# Schematics.net
KiCad netlist of a schematic drawn in Altium Designer
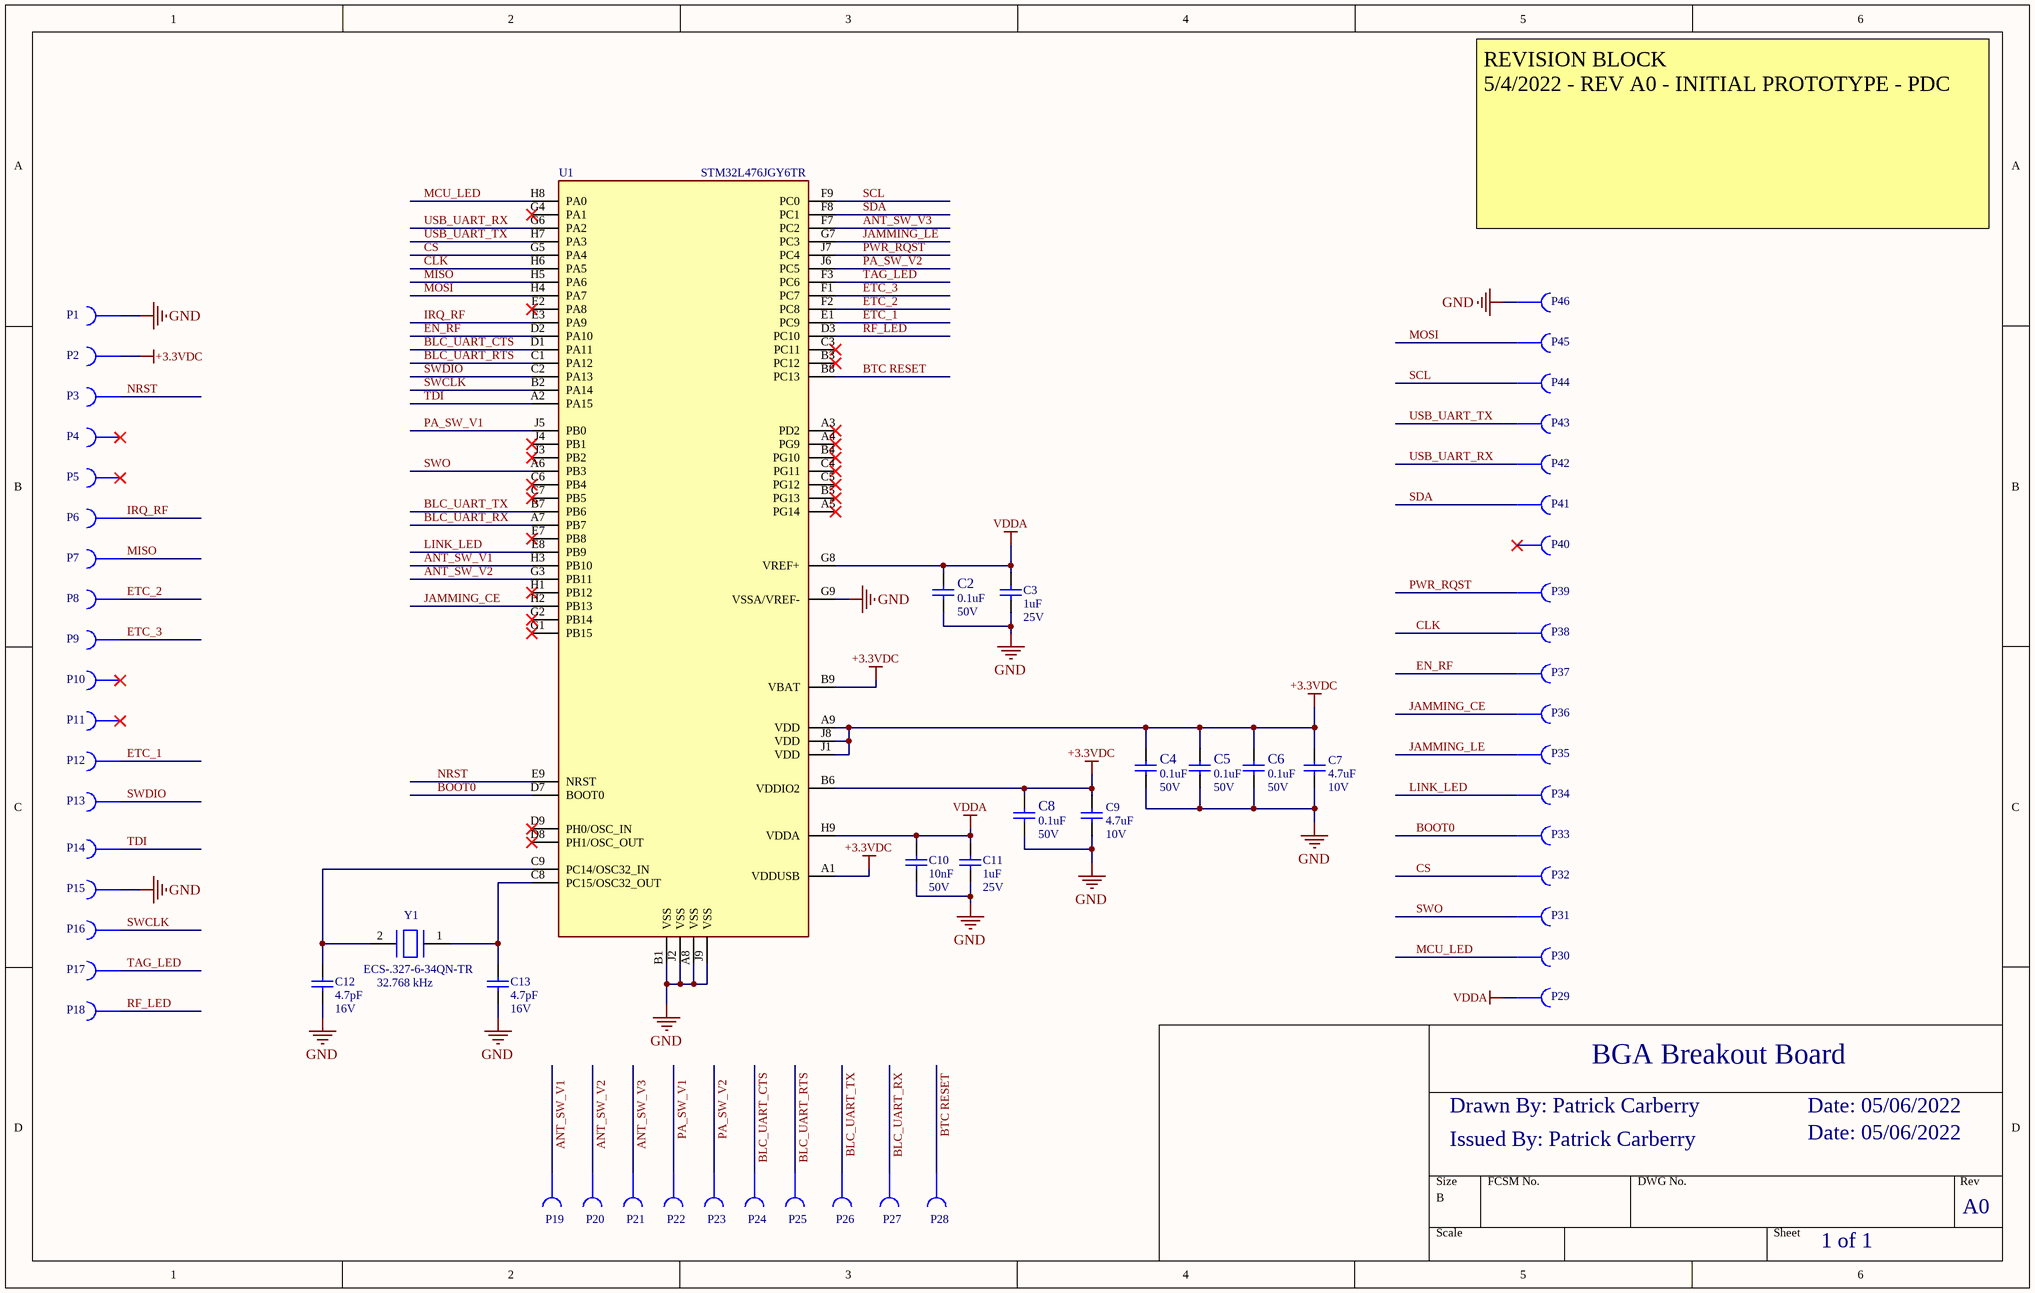
[diagram p0: Schematics.SchDoc]

(export (version "E")
  (design (tool "Eeschema 10.0.6"))
  (components
    (comp (ref "C2")
      (value "0.1uF")
      (footprint "CAP_0402_0.55MM")
      (description "CAP_0.1UF_50V_20%_0402")
      (fields
        (field (name "VOLTAGE RATING") "50V")
        (field (name "MANUFACTURER PART NUMBER") "GRM155R71H104KE14J")
        (field (name "MANUFACTURER") "Murata")
      )
      (libsource (lib "Schlib1") (part "CAP_0.1UF_50V_20%_0402"))
    )
    (comp (ref "C3")
      (value "1uF")
      (footprint "CAP_0402_0.55MM")
      (description "CAP_1UF_25V_20%_0402")
      (fields
        (field (name "MANUFACTURER") "Murata")
        (field (name "MANUFACTURER PART NUMBER") "GRM155R61E105MA12D")
        (field (name "VOLTAGE RATING") "25V")
      )
      (libsource (lib "Schlib1") (part "CAP_1UF_25V_20%_0402"))
    )
    (comp (ref "C4")
      (value "0.1uF")
      (footprint "CAP_0402_0.55MM")
      (description "CAP_0.1UF_50V_20%_0402")
      (fields
        (field (name "VOLTAGE RATING") "50V")
        (field (name "MANUFACTURER PART NUMBER") "GRM155R71H104KE14J")
        (field (name "MANUFACTURER") "Murata")
      )
      (libsource (lib "Schlib1") (part "CAP_0.1UF_50V_20%_0402"))
    )
    (comp (ref "C5")
      (value "0.1uF")
      (footprint "CAP_0402_0.55MM")
      (description "CAP_0.1UF_50V_20%_0402")
      (fields
        (field (name "VOLTAGE RATING") "50V")
        (field (name "MANUFACTURER PART NUMBER") "GRM155R71H104KE14J")
        (field (name "MANUFACTURER") "Murata")
      )
      (libsource (lib "Schlib1") (part "CAP_0.1UF_50V_20%_0402"))
    )
    (comp (ref "C6")
      (value "0.1uF")
      (footprint "CAP_0402_0.55MM")
      (description "CAP_0.1UF_50V_20%_0402")
      (fields
        (field (name "VOLTAGE RATING") "50V")
        (field (name "MANUFACTURER PART NUMBER") "GRM155R71H104KE14J")
        (field (name "MANUFACTURER") "Murata")
      )
      (libsource (lib "Schlib1") (part "CAP_0.1UF_50V_20%_0402"))
    )
    (comp (ref "C7")
      (value "4.7uF")
      (footprint "CAP_0402_0.55MM")
      (description "CAP CER 4.7UF 10V X5R 0402")
      (fields
        (field (name "MANUFACTURER") "Samsung Electro-Mechanics")
        (field (name "MANUFACTURER PART NUMBER") "CL05A475KP5NRNC")
        (field (name "VOLTAGE RATING") "10V")
      )
      (libsource (lib "Schlib1") (part "CAP_4.7UF_10V_X5R_0402"))
    )
    (comp (ref "C8")
      (value "0.1uF")
      (footprint "CAP_0402_0.55MM")
      (description "CAP_0.1UF_50V_20%_0402")
      (fields
        (field (name "VOLTAGE RATING") "50V")
        (field (name "MANUFACTURER PART NUMBER") "GRM155R71H104KE14J")
        (field (name "MANUFACTURER") "Murata")
      )
      (libsource (lib "Schlib1") (part "CAP_0.1UF_50V_20%_0402"))
    )
    (comp (ref "C9")
      (value "4.7uF")
      (footprint "CAP_0402_0.55MM")
      (description "CAP CER 4.7UF 10V X5R 0402")
      (fields
        (field (name "MANUFACTURER") "Samsung Electro-Mechanics")
        (field (name "MANUFACTURER PART NUMBER") "CL05A475KP5NRNC")
        (field (name "VOLTAGE RATING") "10V")
      )
      (libsource (lib "Schlib1") (part "CAP_4.7UF_10V_X5R_0402"))
    )
    (comp (ref "C10")
      (value "10nF")
      (footprint "CAP_0402_0.55MM")
      (description "CAP_10NF_50V_10%_0402")
      (fields
        (field (name "MANUFACTURER") "Murata")
        (field (name "MANUFACTURER PART NUMBER") "GCM155R71H103KA55J")
        (field (name "VOLTAGE RATING") "50V")
      )
      (libsource (lib "Schlib1") (part "CAP_10NF_50V_10%_0402"))
    )
    (comp (ref "C11")
      (value "1uF")
      (footprint "CAP_0402_0.55MM")
      (description "CAP_1UF_25V_20%_0402")
      (fields
        (field (name "MANUFACTURER") "Murata")
        (field (name "MANUFACTURER PART NUMBER") "GRM155R61E105MA12D")
        (field (name "VOLTAGE RATING") "25V")
      )
      (libsource (lib "Schlib1") (part "CAP_1UF_25V_20%_0402"))
    )
    (comp (ref "C12")
      (value "4.7pF")
      (footprint "CAP_0402_0.55MM")
      (description "CAP_4.7PF_16V_C0G_0402")
      (fields
        (field (name "MANUFACTURER") "Würth Elektronik")
        (field (name "MANUFACTURER PART NUMBER") "885012005023")
        (field (name "VOLTAGE RATING") "16V")
      )
      (libsource (lib "Schlib1") (part "CAP_4.7PF_16V_C0G_0402"))
    )
    (comp (ref "C13")
      (value "4.7pF")
      (footprint "CAP_0402_0.55MM")
      (description "CAP_4.7PF_16V_C0G_0402")
      (fields
        (field (name "MANUFACTURER") "Würth Elektronik")
        (field (name "MANUFACTURER PART NUMBER") "885012005023")
        (field (name "VOLTAGE RATING") "16V")
      )
      (libsource (lib "Schlib1") (part "CAP_4.7PF_16V_C0G_0402"))
    )
    (comp (ref "P1")
      (value "1-PIN-HDR-GEN")
      (footprint "1X01-PIN")
      (description "Generic through hole")
      (fields (field (name "MANUFACTURER PART NUMBER") "DNP"))
      (libsource (lib "Schlib1") (part "1-PIN-HDR-GEN"))
    )
    (comp (ref "P2")
      (value "1-PIN-HDR-GEN")
      (footprint "1X01-PIN")
      (description "Generic through hole")
      (fields (field (name "MANUFACTURER PART NUMBER") "DNP"))
      (libsource (lib "Schlib1") (part "1-PIN-HDR-GEN"))
    )
    (comp (ref "P3")
      (value "1-PIN-HDR-GEN")
      (footprint "1X01-PIN")
      (description "Generic through hole")
      (fields (field (name "MANUFACTURER PART NUMBER") "DNP"))
      (libsource (lib "Schlib1") (part "1-PIN-HDR-GEN"))
    )
    (comp (ref "P4")
      (value "1-PIN-HDR-GEN")
      (footprint "1X01-PIN")
      (description "Generic through hole")
      (fields (field (name "MANUFACTURER PART NUMBER") "DNP"))
      (libsource (lib "Schlib1") (part "1-PIN-HDR-GEN"))
    )
    (comp (ref "P5")
      (value "1-PIN-HDR-GEN")
      (footprint "1X01-PIN")
      (description "Generic through hole")
      (fields (field (name "MANUFACTURER PART NUMBER") "DNP"))
      (libsource (lib "Schlib1") (part "1-PIN-HDR-GEN"))
    )
    (comp (ref "P6")
      (value "1-PIN-HDR-GEN")
      (footprint "1X01-PIN")
      (description "Generic through hole")
      (fields (field (name "MANUFACTURER PART NUMBER") "DNP"))
      (libsource (lib "Schlib1") (part "1-PIN-HDR-GEN"))
    )
    (comp (ref "P7")
      (value "1-PIN-HDR-GEN")
      (footprint "1X01-PIN")
      (description "Generic through hole")
      (fields (field (name "MANUFACTURER PART NUMBER") "DNP"))
      (libsource (lib "Schlib1") (part "1-PIN-HDR-GEN"))
    )
    (comp (ref "P8")
      (value "1-PIN-HDR-GEN")
      (footprint "1X01-PIN")
      (description "Generic through hole")
      (fields (field (name "MANUFACTURER PART NUMBER") "DNP"))
      (libsource (lib "Schlib1") (part "1-PIN-HDR-GEN"))
    )
    (comp (ref "P9")
      (value "1-PIN-HDR-GEN")
      (footprint "1X01-PIN")
      (description "Generic through hole")
      (fields (field (name "MANUFACTURER PART NUMBER") "DNP"))
      (libsource (lib "Schlib1") (part "1-PIN-HDR-GEN"))
    )
    (comp (ref "P10")
      (value "1-PIN-HDR-GEN")
      (footprint "1X01-PIN")
      (description "Generic through hole")
      (fields (field (name "MANUFACTURER PART NUMBER") "DNP"))
      (libsource (lib "Schlib1") (part "1-PIN-HDR-GEN"))
    )
    (comp (ref "P11")
      (value "1-PIN-HDR-GEN")
      (footprint "1X01-PIN")
      (description "Generic through hole")
      (fields (field (name "MANUFACTURER PART NUMBER") "DNP"))
      (libsource (lib "Schlib1") (part "1-PIN-HDR-GEN"))
    )
    (comp (ref "P12")
      (value "1-PIN-HDR-GEN")
      (footprint "1X01-PIN")
      (description "Generic through hole")
      (fields (field (name "MANUFACTURER PART NUMBER") "DNP"))
      (libsource (lib "Schlib1") (part "1-PIN-HDR-GEN"))
    )
    (comp (ref "P13")
      (value "1-PIN-HDR-GEN")
      (footprint "1X01-PIN")
      (description "Generic through hole")
      (fields (field (name "MANUFACTURER PART NUMBER") "DNP"))
      (libsource (lib "Schlib1") (part "1-PIN-HDR-GEN"))
    )
    (comp (ref "P14")
      (value "1-PIN-HDR-GEN")
      (footprint "1X01-PIN")
      (description "Generic through hole")
      (fields (field (name "MANUFACTURER PART NUMBER") "DNP"))
      (libsource (lib "Schlib1") (part "1-PIN-HDR-GEN"))
    )
    (comp (ref "P15")
      (value "1-PIN-HDR-GEN")
      (footprint "1X01-PIN")
      (description "Generic through hole")
      (fields (field (name "MANUFACTURER PART NUMBER") "DNP"))
      (libsource (lib "") (part "1-PIN-HDR-GEN_1"))
    )
    (comp (ref "P16")
      (value "1-PIN-HDR-GEN")
      (footprint "1X01-PIN")
      (description "Generic through hole")
      (fields (field (name "MANUFACTURER PART NUMBER") "DNP"))
      (libsource (lib "") (part "1-PIN-HDR-GEN_1"))
    )
    (comp (ref "P17")
      (value "1-PIN-HDR-GEN")
      (footprint "1X01-PIN")
      (description "Generic through hole")
      (fields (field (name "MANUFACTURER PART NUMBER") "DNP"))
      (libsource (lib "") (part "1-PIN-HDR-GEN_1"))
    )
    (comp (ref "P18")
      (value "1-PIN-HDR-GEN")
      (footprint "1X01-PIN")
      (description "Generic through hole")
      (fields (field (name "MANUFACTURER PART NUMBER") "DNP"))
      (libsource (lib "") (part "1-PIN-HDR-GEN_1"))
    )
    (comp (ref "P19")
      (value "1-PIN-HDR-GEN")
      (footprint "1X01-PIN")
      (description "Generic through hole")
      (fields (field (name "MANUFACTURER PART NUMBER") "DNP"))
      (libsource (lib "Schlib1") (part "1-PIN-HDR-GEN"))
    )
    (comp (ref "P20")
      (value "1-PIN-HDR-GEN")
      (footprint "1X01-PIN")
      (description "Generic through hole")
      (fields (field (name "MANUFACTURER PART NUMBER") "DNP"))
      (libsource (lib "Schlib1") (part "1-PIN-HDR-GEN"))
    )
    (comp (ref "P21")
      (value "1-PIN-HDR-GEN")
      (footprint "1X01-PIN")
      (description "Generic through hole")
      (fields (field (name "MANUFACTURER PART NUMBER") "DNP"))
      (libsource (lib "Schlib1") (part "1-PIN-HDR-GEN"))
    )
    (comp (ref "P22")
      (value "1-PIN-HDR-GEN")
      (footprint "1X01-PIN")
      (description "Generic through hole")
      (fields (field (name "MANUFACTURER PART NUMBER") "DNP"))
      (libsource (lib "Schlib1") (part "1-PIN-HDR-GEN"))
    )
    (comp (ref "P23")
      (value "1-PIN-HDR-GEN")
      (footprint "1X01-PIN")
      (description "Generic through hole")
      (fields (field (name "MANUFACTURER PART NUMBER") "DNP"))
      (libsource (lib "Schlib1") (part "1-PIN-HDR-GEN"))
    )
    (comp (ref "P24")
      (value "1-PIN-HDR-GEN")
      (footprint "1X01-PIN")
      (description "Generic through hole")
      (fields (field (name "MANUFACTURER PART NUMBER") "DNP"))
      (libsource (lib "Schlib1") (part "1-PIN-HDR-GEN"))
    )
    (comp (ref "P25")
      (value "1-PIN-HDR-GEN")
      (footprint "1X01-PIN")
      (description "Generic through hole")
      (fields (field (name "MANUFACTURER PART NUMBER") "DNP"))
      (libsource (lib "Schlib1") (part "1-PIN-HDR-GEN"))
    )
    (comp (ref "P26")
      (value "1-PIN-HDR-GEN")
      (footprint "1X01-PIN")
      (description "Generic through hole")
      (fields (field (name "MANUFACTURER PART NUMBER") "DNP"))
      (libsource (lib "Schlib1") (part "1-PIN-HDR-GEN"))
    )
    (comp (ref "P27")
      (value "1-PIN-HDR-GEN")
      (footprint "1X01-PIN")
      (description "Generic through hole")
      (fields (field (name "MANUFACTURER PART NUMBER") "DNP"))
      (libsource (lib "Schlib1") (part "1-PIN-HDR-GEN"))
    )
    (comp (ref "P28")
      (value "1-PIN-HDR-GEN")
      (footprint "1X01-PIN")
      (description "Generic through hole")
      (fields (field (name "MANUFACTURER PART NUMBER") "DNP"))
      (libsource (lib "Schlib1") (part "1-PIN-HDR-GEN"))
    )
    (comp (ref "P29")
      (value "1-PIN-HDR-GEN")
      (footprint "1X01-PIN")
      (description "Generic through hole")
      (fields (field (name "MANUFACTURER PART NUMBER") "DNP"))
      (libsource (lib "Schlib1") (part "1-PIN-HDR-GEN"))
    )
    (comp (ref "P30")
      (value "1-PIN-HDR-GEN")
      (footprint "1X01-PIN")
      (description "Generic through hole")
      (fields (field (name "MANUFACTURER PART NUMBER") "DNP"))
      (libsource (lib "Schlib1") (part "1-PIN-HDR-GEN"))
    )
    (comp (ref "P31")
      (value "1-PIN-HDR-GEN")
      (footprint "1X01-PIN")
      (description "Generic through hole")
      (fields (field (name "MANUFACTURER PART NUMBER") "DNP"))
      (libsource (lib "Schlib1") (part "1-PIN-HDR-GEN"))
    )
    (comp (ref "P32")
      (value "1-PIN-HDR-GEN")
      (footprint "1X01-PIN")
      (description "Generic through hole")
      (fields (field (name "MANUFACTURER PART NUMBER") "DNP"))
      (libsource (lib "Schlib1") (part "1-PIN-HDR-GEN"))
    )
    (comp (ref "P33")
      (value "1-PIN-HDR-GEN")
      (footprint "1X01-PIN")
      (description "Generic through hole")
      (fields (field (name "MANUFACTURER PART NUMBER") "DNP"))
      (libsource (lib "Schlib1") (part "1-PIN-HDR-GEN"))
    )
    (comp (ref "P34")
      (value "1-PIN-HDR-GEN")
      (footprint "1X01-PIN")
      (description "Generic through hole")
      (fields (field (name "MANUFACTURER PART NUMBER") "DNP"))
      (libsource (lib "Schlib1") (part "1-PIN-HDR-GEN"))
    )
    (comp (ref "P35")
      (value "1-PIN-HDR-GEN")
      (footprint "1X01-PIN")
      (description "Generic through hole")
      (fields (field (name "MANUFACTURER PART NUMBER") "DNP"))
      (libsource (lib "Schlib1") (part "1-PIN-HDR-GEN"))
    )
    (comp (ref "P36")
      (value "1-PIN-HDR-GEN")
      (footprint "1X01-PIN")
      (description "Generic through hole")
      (fields (field (name "MANUFACTURER PART NUMBER") "DNP"))
      (libsource (lib "Schlib1") (part "1-PIN-HDR-GEN"))
    )
    (comp (ref "P37")
      (value "1-PIN-HDR-GEN")
      (footprint "1X01-PIN")
      (description "Generic through hole")
      (fields (field (name "MANUFACTURER PART NUMBER") "DNP"))
      (libsource (lib "Schlib1") (part "1-PIN-HDR-GEN"))
    )
    (comp (ref "P38")
      (value "1-PIN-HDR-GEN")
      (footprint "1X01-PIN")
      (description "Generic through hole")
      (fields (field (name "MANUFACTURER PART NUMBER") "DNP"))
      (libsource (lib "Schlib1") (part "1-PIN-HDR-GEN"))
    )
    (comp (ref "P39")
      (value "1-PIN-HDR-GEN")
      (footprint "1X01-PIN")
      (description "Generic through hole")
      (fields (field (name "MANUFACTURER PART NUMBER") "DNP"))
      (libsource (lib "Schlib1") (part "1-PIN-HDR-GEN"))
    )
    (comp (ref "P40")
      (value "1-PIN-HDR-GEN")
      (footprint "1X01-PIN")
      (description "Generic through hole")
      (fields (field (name "MANUFACTURER PART NUMBER") "DNP"))
      (libsource (lib "Schlib1") (part "1-PIN-HDR-GEN"))
    )
    (comp (ref "P41")
      (value "1-PIN-HDR-GEN")
      (footprint "1X01-PIN")
      (description "Generic through hole")
      (fields (field (name "MANUFACTURER PART NUMBER") "DNP"))
      (libsource (lib "Schlib1") (part "1-PIN-HDR-GEN"))
    )
    (comp (ref "P42")
      (value "1-PIN-HDR-GEN")
      (footprint "1X01-PIN")
      (description "Generic through hole")
      (fields (field (name "MANUFACTURER PART NUMBER") "DNP"))
      (libsource (lib "Schlib1") (part "1-PIN-HDR-GEN"))
    )
    (comp (ref "P43")
      (value "1-PIN-HDR-GEN")
      (footprint "1X01-PIN")
      (description "Generic through hole")
      (fields (field (name "MANUFACTURER PART NUMBER") "DNP"))
      (libsource (lib "Schlib1") (part "1-PIN-HDR-GEN"))
    )
    (comp (ref "P44")
      (value "1-PIN-HDR-GEN")
      (footprint "1X01-PIN")
      (description "Generic through hole")
      (fields (field (name "MANUFACTURER PART NUMBER") "DNP"))
      (libsource (lib "Schlib1") (part "1-PIN-HDR-GEN"))
    )
    (comp (ref "P45")
      (value "1-PIN-HDR-GEN")
      (footprint "1X01-PIN")
      (description "Generic through hole")
      (fields (field (name "MANUFACTURER PART NUMBER") "DNP"))
      (libsource (lib "Schlib1") (part "1-PIN-HDR-GEN"))
    )
    (comp (ref "P46")
      (value "1-PIN-HDR-GEN")
      (footprint "1X01-PIN")
      (description "Generic through hole")
      (fields (field (name "MANUFACTURER PART NUMBER") "DNP"))
      (libsource (lib "Schlib1") (part "1-PIN-HDR-GEN"))
    )
    (comp (ref "U1")
      (value "STM32L476JGY6TR")
      (footprint "BGA72C40P9X9_441X374X56")
      (fields (field (name "MANUFACTURER") "STMicroelectronics"))
      (libsource (lib "Schlib1") (part "MCU_ARM_CM4_80MHZ_STM32L476JGY6TR"))
    )
    (comp (ref "Y1")
      (value "ECS-.327-6-34QN-TR")
      (footprint "CRY_3.2X1.5_2SMD")
      (description "32.768 kHz ±20ppm Crystal 6pF 70 kOhms 2-SMD, No Lead")
      (fields (field (name "MANUFACTURER") "ECS") (field (name "ALTIUM_VALUE") "32.768 kHz"))
      (libsource (lib "Schlib1") (part "CRY_32.768KHZ_70K_4PF_2SMD"))
    )
  )
  (nets
    (net (code "1") (name "+3.3VDC") (class "Default")
      (node (ref "C4") (pin "2") (pinfunction "2_2") (pintype "passive"))
      (node (ref "C5") (pin "2") (pinfunction "2_2") (pintype "passive"))
      (node (ref "C6") (pin "2") (pinfunction "2_2") (pintype "passive"))
      (node (ref "C7") (pin "1") (pinfunction "1_1") (pintype "passive"))
      (node (ref "C8") (pin "2") (pinfunction "2_2") (pintype "passive"))
      (node (ref "C9") (pin "1") (pinfunction "1_1") (pintype "passive"))
      (node (ref "P2") (pin "1") (pinfunction "P$1_1") (pintype "passive"))
      (node (ref "U1") (pin "A1") (pinfunction "VDDUSB_A1") (pintype "power_in"))
      (node (ref "U1") (pin "A9") (pinfunction "VDD_A9") (pintype "power_in"))
      (node (ref "U1") (pin "B6") (pinfunction "VDDIO2_B6") (pintype "power_in"))
      (node (ref "U1") (pin "B9") (pinfunction "VBAT_B9") (pintype "power_in"))
      (node (ref "U1") (pin "J1") (pinfunction "VDD_J1") (pintype "power_in"))
      (node (ref "U1") (pin "J8") (pinfunction "VDD_J8") (pintype "power_in"))
    )
    (net (code "2") (name "/ANT_SW_V1") (class "Default")
      (node (ref "P19") (pin "1") (pinfunction "P$1_1") (pintype "passive"))
      (node (ref "U1") (pin "H3") (pinfunction "PB10_H3") (pintype "passive"))
    )
    (net (code "3") (name "/ANT_SW_V2") (class "Default")
      (node (ref "P20") (pin "1") (pinfunction "P$1_1") (pintype "passive"))
      (node (ref "U1") (pin "G3") (pinfunction "PB11_G3") (pintype "passive"))
    )
    (net (code "4") (name "/ANT_SW_V3") (class "Default")
      (node (ref "P21") (pin "1") (pinfunction "P$1_1") (pintype "passive"))
      (node (ref "U1") (pin "F7") (pinfunction "PC2_F7") (pintype "passive"))
    )
    (net (code "5") (name "/BLC_UART_CTS") (class "Default")
      (node (ref "P24") (pin "1") (pinfunction "P$1_1") (pintype "passive"))
      (node (ref "U1") (pin "D1") (pinfunction "PA11_D1") (pintype "passive"))
    )
    (net (code "6") (name "/BLC_UART_RTS") (class "Default")
      (node (ref "P25") (pin "1") (pinfunction "P$1_1") (pintype "passive"))
      (node (ref "U1") (pin "C1") (pinfunction "PA12_C1") (pintype "passive"))
    )
    (net (code "7") (name "/BLC_UART_RX") (class "Default")
      (node (ref "P27") (pin "1") (pinfunction "P$1_1") (pintype "passive"))
      (node (ref "U1") (pin "A7") (pinfunction "PB7_A7") (pintype "passive"))
    )
    (net (code "8") (name "/BLC_UART_TX") (class "Default")
      (node (ref "P26") (pin "1") (pinfunction "P$1_1") (pintype "passive"))
      (node (ref "U1") (pin "B7") (pinfunction "PB6_B7") (pintype "passive"))
    )
    (net (code "9") (name "/BOOT0") (class "Default")
      (node (ref "P33") (pin "1") (pinfunction "P$1_1") (pintype "passive"))
      (node (ref "U1") (pin "D7") (pinfunction "BOOT0_D7") (pintype "passive"))
    )
    (net (code "10") (name "/BTC RESET") (class "Default")
      (node (ref "P28") (pin "1") (pinfunction "P$1_1") (pintype "passive"))
      (node (ref "U1") (pin "B8") (pinfunction "PC13_B8") (pintype "passive"))
    )
    (net (code "11") (name "/CLK") (class "Default")
      (node (ref "P38") (pin "1") (pinfunction "P$1_1") (pintype "passive"))
      (node (ref "U1") (pin "H6") (pinfunction "PA5_H6") (pintype "passive"))
    )
    (net (code "12") (name "/CS") (class "Default")
      (node (ref "P32") (pin "1") (pinfunction "P$1_1") (pintype "passive"))
      (node (ref "U1") (pin "G5") (pinfunction "PA4_G5") (pintype "passive"))
    )
    (net (code "13") (name "/EN_RF") (class "Default")
      (node (ref "P37") (pin "1") (pinfunction "P$1_1") (pintype "passive"))
      (node (ref "U1") (pin "D2") (pinfunction "PA10_D2") (pintype "passive"))
    )
    (net (code "14") (name "/ETC_1") (class "Default")
      (node (ref "P12") (pin "1") (pinfunction "P$1_1") (pintype "passive"))
      (node (ref "U1") (pin "E1") (pinfunction "PC9_E1") (pintype "passive"))
    )
    (net (code "15") (name "/ETC_2") (class "Default")
      (node (ref "P8") (pin "1") (pinfunction "P$1_1") (pintype "passive"))
      (node (ref "U1") (pin "F2") (pinfunction "PC8_F2") (pintype "passive"))
    )
    (net (code "16") (name "/ETC_3") (class "Default")
      (node (ref "P9") (pin "1") (pinfunction "P$1_1") (pintype "passive"))
      (node (ref "U1") (pin "F1") (pinfunction "PC7_F1") (pintype "passive"))
    )
    (net (code "17") (name "/IRQ_RF") (class "Default")
      (node (ref "P6") (pin "1") (pinfunction "P$1_1") (pintype "passive"))
      (node (ref "U1") (pin "E3") (pinfunction "PA9_E3") (pintype "passive"))
    )
    (net (code "18") (name "/JAMMING_CE") (class "Default")
      (node (ref "P36") (pin "1") (pinfunction "P$1_1") (pintype "passive"))
      (node (ref "U1") (pin "H2") (pinfunction "PB13_H2") (pintype "passive"))
    )
    (net (code "19") (name "/JAMMING_LE") (class "Default")
      (node (ref "P35") (pin "1") (pinfunction "P$1_1") (pintype "passive"))
      (node (ref "U1") (pin "G7") (pinfunction "PC3_G7") (pintype "passive"))
    )
    (net (code "20") (name "/LINK_LED") (class "Default")
      (node (ref "P34") (pin "1") (pinfunction "P$1_1") (pintype "passive"))
      (node (ref "U1") (pin "E8") (pinfunction "PB9_E8") (pintype "passive"))
    )
    (net (code "21") (name "/MCU_LED") (class "Default")
      (node (ref "P30") (pin "1") (pinfunction "P$1_1") (pintype "passive"))
      (node (ref "U1") (pin "H8") (pinfunction "PA0_H8") (pintype "passive"))
    )
    (net (code "22") (name "/MISO") (class "Default")
      (node (ref "P7") (pin "1") (pinfunction "P$1_1") (pintype "passive"))
      (node (ref "U1") (pin "H5") (pinfunction "PA6_H5") (pintype "passive"))
    )
    (net (code "23") (name "/MOSI") (class "Default")
      (node (ref "P45") (pin "1") (pinfunction "P$1_1") (pintype "passive"))
      (node (ref "U1") (pin "H4") (pinfunction "PA7_H4") (pintype "passive"))
    )
    (net (code "24") (name "/NRST") (class "Default")
      (node (ref "P3") (pin "1") (pinfunction "P$1_1") (pintype "passive"))
      (node (ref "U1") (pin "E9") (pinfunction "NRST_E9") (pintype "passive"))
    )
    (net (code "25") (name "/PA_SW_V1") (class "Default")
      (node (ref "P22") (pin "1") (pinfunction "P$1_1") (pintype "passive"))
      (node (ref "U1") (pin "J5") (pinfunction "PB0_J5") (pintype "passive"))
    )
    (net (code "26") (name "/PA_SW_V2") (class "Default")
      (node (ref "P23") (pin "1") (pinfunction "P$1_1") (pintype "passive"))
      (node (ref "U1") (pin "J6") (pinfunction "PC5_J6") (pintype "passive"))
    )
    (net (code "27") (name "/PWR_RQST") (class "Default")
      (node (ref "P39") (pin "1") (pinfunction "P$1_1") (pintype "passive"))
      (node (ref "U1") (pin "J7") (pinfunction "PC4_J7") (pintype "passive"))
    )
    (net (code "28") (name "/RF_LED") (class "Default")
      (node (ref "P18") (pin "1") (pinfunction "P$1_1") (pintype "passive"))
      (node (ref "U1") (pin "D3") (pinfunction "PC10_D3") (pintype "passive"))
    )
    (net (code "29") (name "/SCL") (class "Default")
      (node (ref "P44") (pin "1") (pinfunction "P$1_1") (pintype "passive"))
      (node (ref "U1") (pin "F9") (pinfunction "PC0_F9") (pintype "passive"))
    )
    (net (code "30") (name "/SDA") (class "Default")
      (node (ref "P41") (pin "1") (pinfunction "P$1_1") (pintype "passive"))
      (node (ref "U1") (pin "F8") (pinfunction "PC1_F8") (pintype "passive"))
    )
    (net (code "31") (name "/SWCLK") (class "Default")
      (node (ref "P16") (pin "1") (pinfunction "P$1_1") (pintype "passive"))
      (node (ref "U1") (pin "B2") (pinfunction "PA14_B2") (pintype "passive"))
    )
    (net (code "32") (name "/SWDIO") (class "Default")
      (node (ref "P13") (pin "1") (pinfunction "P$1_1") (pintype "passive"))
      (node (ref "U1") (pin "C2") (pinfunction "PA13_C2") (pintype "passive"))
    )
    (net (code "33") (name "/SWO") (class "Default")
      (node (ref "P31") (pin "1") (pinfunction "P$1_1") (pintype "passive"))
      (node (ref "U1") (pin "A6") (pinfunction "PB3_A6") (pintype "passive"))
    )
    (net (code "34") (name "/TAG_LED") (class "Default")
      (node (ref "P17") (pin "1") (pinfunction "P$1_1") (pintype "passive"))
      (node (ref "U1") (pin "F3") (pinfunction "PC6_F3") (pintype "passive"))
    )
    (net (code "35") (name "/TDI") (class "Default")
      (node (ref "P14") (pin "1") (pinfunction "P$1_1") (pintype "passive"))
      (node (ref "U1") (pin "A2") (pinfunction "PA15_A2") (pintype "passive"))
    )
    (net (code "36") (name "/USB_UART_RX") (class "Default")
      (node (ref "P42") (pin "1") (pinfunction "P$1_1") (pintype "passive"))
      (node (ref "U1") (pin "G6") (pinfunction "PA2_G6") (pintype "passive"))
    )
    (net (code "37") (name "/USB_UART_TX") (class "Default")
      (node (ref "P43") (pin "1") (pinfunction "P$1_1") (pintype "passive"))
      (node (ref "U1") (pin "H7") (pinfunction "PA3_H7") (pintype "passive"))
    )
    (net (code "38") (name "GND") (class "Default")
      (node (ref "C10") (pin "2") (pinfunction "2_2") (pintype "passive"))
      (node (ref "C11") (pin "2") (pinfunction "2_2") (pintype "passive"))
      (node (ref "C12") (pin "2") (pinfunction "2_2") (pintype "passive"))
      (node (ref "C13") (pin "2") (pinfunction "2_2") (pintype "passive"))
      (node (ref "C2") (pin "1") (pinfunction "1_1") (pintype "passive"))
      (node (ref "C3") (pin "2") (pinfunction "2_2") (pintype "passive"))
      (node (ref "C4") (pin "1") (pinfunction "1_1") (pintype "passive"))
      (node (ref "C5") (pin "1") (pinfunction "1_1") (pintype "passive"))
      (node (ref "C6") (pin "1") (pinfunction "1_1") (pintype "passive"))
      (node (ref "C7") (pin "2") (pinfunction "2_2") (pintype "passive"))
      (node (ref "C8") (pin "1") (pinfunction "1_1") (pintype "passive"))
      (node (ref "C9") (pin "2") (pinfunction "2_2") (pintype "passive"))
      (node (ref "P1") (pin "1") (pinfunction "P$1_1") (pintype "passive"))
      (node (ref "P15") (pin "1") (pinfunction "P$1_1") (pintype "passive"))
      (node (ref "P46") (pin "1") (pinfunction "P$1_1") (pintype "passive"))
      (node (ref "U1") (pin "A8") (pinfunction "VSS_A8") (pintype "power_in"))
      (node (ref "U1") (pin "B1") (pinfunction "VSS_B1") (pintype "power_in"))
      (node (ref "U1") (pin "G9") (pinfunction "VSSA/VREF-_G9") (pintype "power_in"))
      (node (ref "U1") (pin "J2") (pinfunction "VSS_J2") (pintype "power_in"))
      (node (ref "U1") (pin "J9") (pinfunction "VSS_J9") (pintype "power_in"))
    )
    (net (code "39") (name "Net-(U1-PC14{slash}OSC32_IN)") (class "Default")
      (node (ref "C12") (pin "1") (pinfunction "1_1") (pintype "passive"))
      (node (ref "U1") (pin "C9") (pinfunction "PC14/OSC32_IN_C9") (pintype "passive"))
      (node (ref "Y1") (pin "2") (pinfunction "X2_2") (pintype "passive"))
    )
    (net (code "40") (name "Net-(U1-PC15{slash}OSC32_OUT)") (class "Default")
      (node (ref "C13") (pin "1") (pinfunction "1_1") (pintype "passive"))
      (node (ref "U1") (pin "C8") (pinfunction "PC15/OSC32_OUT_C8") (pintype "passive"))
      (node (ref "Y1") (pin "1") (pinfunction "X1_1") (pintype "passive"))
    )
    (net (code "41") (name "VDDA") (class "Default")
      (node (ref "C10") (pin "1") (pinfunction "1_1") (pintype "passive"))
      (node (ref "C11") (pin "1") (pinfunction "1_1") (pintype "passive"))
      (node (ref "C2") (pin "2") (pinfunction "2_2") (pintype "passive"))
      (node (ref "C3") (pin "1") (pinfunction "1_1") (pintype "passive"))
      (node (ref "P29") (pin "1") (pinfunction "P$1_1") (pintype "passive"))
      (node (ref "U1") (pin "G8") (pinfunction "VREF+_G8") (pintype "power_in"))
      (node (ref "U1") (pin "H9") (pinfunction "VDDA_H9") (pintype "power_in"))
    )
    (net (code "42") (name "unconnected-(P4-P$1-Pad1)") (class "Default")
      (node (ref "P4") (pin "1") (pinfunction "P$1_1") (pintype "passive+no_connect"))
    )
    (net (code "43") (name "unconnected-(P5-P$1-Pad1)") (class "Default")
      (node (ref "P5") (pin "1") (pinfunction "P$1_1") (pintype "passive+no_connect"))
    )
    (net (code "44") (name "unconnected-(P10-P$1-Pad1)") (class "Default")
      (node (ref "P10") (pin "1") (pinfunction "P$1_1") (pintype "passive+no_connect"))
    )
    (net (code "45") (name "unconnected-(P11-P$1-Pad1)") (class "Default")
      (node (ref "P11") (pin "1") (pinfunction "P$1_1") (pintype "passive+no_connect"))
    )
    (net (code "46") (name "unconnected-(P40-P$1-Pad1)") (class "Default")
      (node (ref "P40") (pin "1") (pinfunction "P$1_1") (pintype "passive+no_connect"))
    )
    (net (code "47") (name "unconnected-(U1-PA1-PadG4)") (class "Default")
      (node (ref "U1") (pin "G4") (pinfunction "PA1_G4") (pintype "passive+no_connect"))
    )
    (net (code "48") (name "unconnected-(U1-PA8-PadE2)") (class "Default")
      (node (ref "U1") (pin "E2") (pinfunction "PA8_E2") (pintype "passive+no_connect"))
    )
    (net (code "49") (name "unconnected-(U1-PB1-PadJ4)") (class "Default")
      (node (ref "U1") (pin "J4") (pinfunction "PB1_J4") (pintype "passive+no_connect"))
    )
    (net (code "50") (name "unconnected-(U1-PB2-PadJ3)") (class "Default")
      (node (ref "U1") (pin "J3") (pinfunction "PB2_J3") (pintype "passive+no_connect"))
    )
    (net (code "51") (name "unconnected-(U1-PB4-PadC6)") (class "Default")
      (node (ref "U1") (pin "C6") (pinfunction "PB4_C6") (pintype "passive+no_connect"))
    )
    (net (code "52") (name "unconnected-(U1-PB5-PadC7)") (class "Default")
      (node (ref "U1") (pin "C7") (pinfunction "PB5_C7") (pintype "passive+no_connect"))
    )
    (net (code "53") (name "unconnected-(U1-PB8-PadE7)") (class "Default")
      (node (ref "U1") (pin "E7") (pinfunction "PB8_E7") (pintype "passive+no_connect"))
    )
    (net (code "54") (name "unconnected-(U1-PB12-PadH1)") (class "Default")
      (node (ref "U1") (pin "H1") (pinfunction "PB12_H1") (pintype "passive+no_connect"))
    )
    (net (code "55") (name "unconnected-(U1-PB14-PadG2)") (class "Default")
      (node (ref "U1") (pin "G2") (pinfunction "PB14_G2") (pintype "passive+no_connect"))
    )
    (net (code "56") (name "unconnected-(U1-PB15-PadG1)") (class "Default")
      (node (ref "U1") (pin "G1") (pinfunction "PB15_G1") (pintype "passive+no_connect"))
    )
    (net (code "57") (name "unconnected-(U1-PC11-PadC3)") (class "Default")
      (node (ref "U1") (pin "C3") (pinfunction "PC11_C3") (pintype "passive+no_connect"))
    )
    (net (code "58") (name "unconnected-(U1-PC12-PadB3)") (class "Default")
      (node (ref "U1") (pin "B3") (pinfunction "PC12_B3") (pintype "passive+no_connect"))
    )
    (net (code "59") (name "unconnected-(U1-PD2-PadA3)") (class "Default")
      (node (ref "U1") (pin "A3") (pinfunction "PD2_A3") (pintype "passive+no_connect"))
    )
    (net (code "60") (name "unconnected-(U1-PG9-PadA4)") (class "Default")
      (node (ref "U1") (pin "A4") (pinfunction "PG9_A4") (pintype "passive+no_connect"))
    )
    (net (code "61") (name "unconnected-(U1-PG10-PadB4)") (class "Default")
      (node (ref "U1") (pin "B4") (pinfunction "PG10_B4") (pintype "passive+no_connect"))
    )
    (net (code "62") (name "unconnected-(U1-PG11-PadC4)") (class "Default")
      (node (ref "U1") (pin "C4") (pinfunction "PG11_C4") (pintype "passive+no_connect"))
    )
    (net (code "63") (name "unconnected-(U1-PG12-PadC5)") (class "Default")
      (node (ref "U1") (pin "C5") (pinfunction "PG12_C5") (pintype "passive+no_connect"))
    )
    (net (code "64") (name "unconnected-(U1-PG13-PadB5)") (class "Default")
      (node (ref "U1") (pin "B5") (pinfunction "PG13_B5") (pintype "passive+no_connect"))
    )
    (net (code "65") (name "unconnected-(U1-PG14-PadA5)") (class "Default")
      (node (ref "U1") (pin "A5") (pinfunction "PG14_A5") (pintype "passive+no_connect"))
    )
    (net (code "66") (name "unconnected-(U1-PH0{slash}OSC_IN-PadD9)") (class "Default")
      (node (ref "U1") (pin "D9") (pinfunction "PH0/OSC_IN_D9") (pintype "passive+no_connect"))
    )
    (net (code "67") (name "unconnected-(U1-PH1{slash}OSC_OUT-PadD8)") (class "Default")
      (node (ref "U1") (pin "D8") (pinfunction "PH1/OSC_OUT_D8") (pintype "passive+no_connect"))
    )
  )
)
